# sensor_de_corriente.net
KiCad netlist of a schematic drawn in Altium Designer
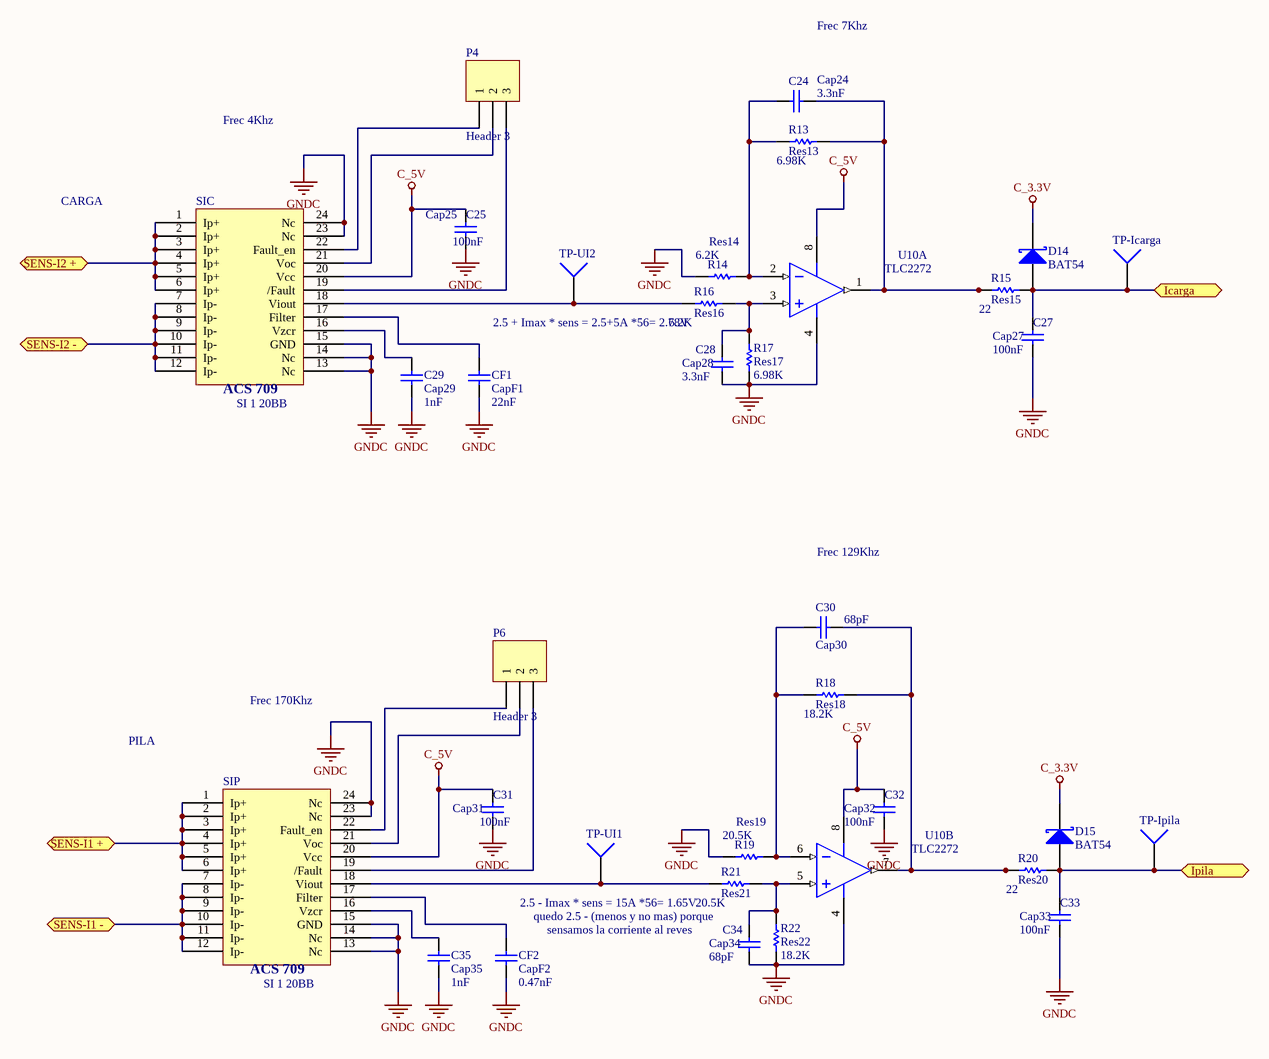
[diagram p0: sensor de corriente.SchDoc]

(export (version "E")
  (design (tool "Eeschema 10.0.6"))
  (components
    (comp (ref "C24")
      (value "Cap24")
      (footprint "RAD-0.1")
      (description "THRU MULTICAPA 50V")
      (fields (field (name "ALTIUM_VALUE") "3.3nF") (field (name "PUBLISHER") "Altium Limited"))
      (libsource (lib "Miscellaneous Devices") (part "Cap"))
    )
    (comp (ref "C25")
      (value "Cap25")
      (footprint "8-1206")
      (description "SMD MULTICAPA 50V")
      (fields (field (name "ALTIUM_VALUE") "100nF") (field (name "PUBLISHER") "Altium Limited"))
      (libsource (lib "Miscellaneous Devices") (part "Cap"))
    )
    (comp (ref "C27")
      (value "Cap27")
      (footprint "8-1206")
      (description "SMD MULTICAPA 50V")
      (fields (field (name "ALTIUM_VALUE") "100nF") (field (name "PUBLISHER") "Altium Limited"))
      (libsource (lib "Miscellaneous Devices") (part "Cap"))
    )
    (comp (ref "C28")
      (value "Cap28")
      (footprint "RAD-0.1")
      (description "THRU MULTICAPA 50V")
      (fields (field (name "ALTIUM_VALUE") "3.3nF") (field (name "PUBLISHER") "Altium Limited"))
      (libsource (lib "Miscellaneous Devices") (part "Cap"))
    )
    (comp (ref "C29")
      (value "Cap29")
      (footprint "8-1206")
      (description "SMD MULTICAPA 50V")
      (fields (field (name "ALTIUM_VALUE") "1nF") (field (name "PUBLISHER") "Altium Limited"))
      (libsource (lib "Miscellaneous Devices") (part "Cap"))
    )
    (comp (ref "C30")
      (value "Cap30")
      (footprint "RAD-0.1")
      (description "THRU MULTICAPA 50V")
      (fields (field (name "ALTIUM_VALUE") "68pF") (field (name "PUBLISHER") "Altium Limited"))
      (libsource (lib "Miscellaneous Devices") (part "Cap"))
    )
    (comp (ref "C31")
      (value "Cap31")
      (footprint "8-1206")
      (description "SMD MULTICAPA 50V")
      (fields (field (name "ALTIUM_VALUE") "100nF") (field (name "PUBLISHER") "Altium Limited"))
      (libsource (lib "Miscellaneous Devices") (part "Cap"))
    )
    (comp (ref "C32")
      (value "Cap32")
      (footprint "8-1206")
      (description "SMD MULTICAPA 50V")
      (fields (field (name "ALTIUM_VALUE") "100nF") (field (name "PUBLISHER") "Altium Limited"))
      (libsource (lib "Miscellaneous Devices") (part "Cap"))
    )
    (comp (ref "C33")
      (value "Cap33")
      (footprint "8-1206")
      (description "SMD MULTICAPA 50V")
      (fields (field (name "ALTIUM_VALUE") "100nF") (field (name "PUBLISHER") "Altium Limited"))
      (libsource (lib "Miscellaneous Devices") (part "Cap"))
    )
    (comp (ref "C34")
      (value "Cap34")
      (footprint "RAD-0.1")
      (description "THRU MULTICAPA 50V")
      (fields (field (name "ALTIUM_VALUE") "68pF") (field (name "PUBLISHER") "Altium Limited"))
      (libsource (lib "Miscellaneous Devices") (part "Cap"))
    )
    (comp (ref "C35")
      (value "Cap35")
      (footprint "8-1206")
      (description "SMD MULTICAPA 50V")
      (fields (field (name "ALTIUM_VALUE") "1nF") (field (name "PUBLISHER") "Altium Limited"))
      (libsource (lib "Miscellaneous Devices") (part "Cap"))
    )
    (comp (ref "CF1")
      (value "CapF1")
      (footprint "RAD-0.1")
      (description "SMD MULTICAPA 50V")
      (fields (field (name "ALTIUM_VALUE") "22nF") (field (name "PUBLISHER") "Altium Limited"))
      (libsource (lib "Miscellaneous Devices") (part "Cap"))
    )
    (comp (ref "CF2")
      (value "CapF2")
      (footprint "8-1206")
      (description "SMD MULTICAPA 50V")
      (fields (field (name "ALTIUM_VALUE") "0.47nF") (field (name "PUBLISHER") "Altium Limited"))
      (libsource (lib "Miscellaneous Devices") (part "Cap"))
    )
    (comp (ref "D14")
      (value "BAT54")
      (footprint "SOD123*")
      (description "SMD")
      (fields (field (name "PUBLISHER") "Altium Limited"))
      (libsource (lib "Philips Discrete Diode - Schottky") (part "BAT54"))
    )
    (comp (ref "D15")
      (value "BAT54")
      (footprint "SOD123*")
      (description "Schottky Barrier Diode SMD")
      (fields (field (name "PUBLISHER") "Altium Limited"))
      (libsource (lib "Philips Discrete Diode - Schottky") (part "BAT54"))
    )
    (comp (ref "P4")
      (value "Header 3")
      (footprint "HDR1X3*")
      (description "Header, 3-Pin")
      (fields (field (name "PUBLISHER") "Altium Limited"))
      (libsource (lib "Miscellaneous Connectors") (part "Header 3"))
    )
    (comp (ref "P6")
      (value "Header 3")
      (footprint "HDR1X3*")
      (description "Header, 3-Pin")
      (fields (field (name "PUBLISHER") "Altium Limited"))
      (libsource (lib "Miscellaneous Connectors") (part "Header 3"))
    )
    (comp (ref "R13")
      (value "Res13")
      (footprint "AXIAL-0.4")
      (description "Resistor")
      (fields (field (name "ALTIUM_VALUE") "6.98K") (field (name "PUBLISHER") "Altium Limited"))
      (libsource (lib "Miscellaneous Devices") (part "Res1"))
    )
    (comp (ref "R14")
      (value "Res14")
      (footprint "AXIAL-0.4")
      (description "Resistor")
      (fields (field (name "ALTIUM_VALUE") "6.2K") (field (name "PUBLISHER") "Altium Limited"))
      (libsource (lib "Miscellaneous Devices") (part "Res1"))
    )
    (comp (ref "R15")
      (value "Res15")
      (footprint "8-1206")
      (description "SMD 1206")
      (fields (field (name "ALTIUM_VALUE") "22") (field (name "PUBLISHER") "Altium Limited"))
      (libsource (lib "Miscellaneous Devices") (part "Res1"))
    )
    (comp (ref "R16")
      (value "Res16")
      (footprint "AXIAL-0.4")
      (description "Resistor")
      (fields (field (name "ALTIUM_VALUE") "6.2K") (field (name "PUBLISHER") "Altium Limited"))
      (libsource (lib "Miscellaneous Devices") (part "Res1"))
    )
    (comp (ref "R17")
      (value "Res17")
      (footprint "AXIAL-0.4")
      (description "Resistor")
      (fields (field (name "ALTIUM_VALUE") "6.98K") (field (name "PUBLISHER") "Altium Limited"))
      (libsource (lib "Miscellaneous Devices") (part "Res1"))
    )
    (comp (ref "R18")
      (value "Res18")
      (footprint "AXIAL-0.4")
      (description "Resistor")
      (fields (field (name "ALTIUM_VALUE") "18.2K") (field (name "PUBLISHER") "Altium Limited"))
      (libsource (lib "Miscellaneous Devices") (part "Res1"))
    )
    (comp (ref "R19")
      (value "Res19")
      (footprint "AXIAL-0.4")
      (description "Resistor")
      (fields (field (name "ALTIUM_VALUE") "20.5K") (field (name "PUBLISHER") "Altium Limited"))
      (libsource (lib "Miscellaneous Devices") (part "Res1"))
    )
    (comp (ref "R20")
      (value "Res20")
      (footprint "8-1206")
      (description "SMD 1206")
      (fields (field (name "ALTIUM_VALUE") "22") (field (name "PUBLISHER") "Altium Limited"))
      (libsource (lib "Miscellaneous Devices") (part "Res1"))
    )
    (comp (ref "R21")
      (value "Res21")
      (footprint "AXIAL-0.4")
      (description "Resistor")
      (fields (field (name "ALTIUM_VALUE") "20.5K") (field (name "PUBLISHER") "Altium Limited"))
      (libsource (lib "Miscellaneous Devices") (part "Res1"))
    )
    (comp (ref "R22")
      (value "Res22")
      (footprint "AXIAL-0.4")
      (description "Resistor")
      (fields (field (name "ALTIUM_VALUE") "18.2K") (field (name "PUBLISHER") "Altium Limited"))
      (libsource (lib "Miscellaneous Devices") (part "Res1"))
    )
    (comp (ref "SIC")
      (value "SI 1 20BB")
      (footprint "Sensor Corriente ACS 709")
      (libsource (lib "sensor corriente ACS 709") (part "Component_1"))
    )
    (comp (ref "SIP")
      (value "SI 1 20BB")
      (footprint "Sensor Corriente ACS 709")
      (libsource (lib "sensor corriente ACS 709") (part "Component_1"))
    )
    (comp (ref "TP-Icarga")
      (value "~")
      (footprint "PIN1")
      (description "Socket")
      (fields (field (name "PUBLISHER") "Altium Limited"))
      (libsource (lib "Miscellaneous Connectors") (part "Socket"))
    )
    (comp (ref "TP-Ipila")
      (value "~")
      (footprint "PIN1")
      (description "Socket")
      (fields (field (name "PUBLISHER") "Altium Limited"))
      (libsource (lib "Miscellaneous Connectors") (part "Socket"))
    )
    (comp (ref "TP-UI1")
      (value "~")
      (footprint "PIN1")
      (description "Socket")
      (fields (field (name "PUBLISHER") "Altium Limited"))
      (libsource (lib "Miscellaneous Connectors") (part "Socket"))
    )
    (comp (ref "TP-UI2")
      (value "~")
      (footprint "PIN1")
      (description "Socket")
      (fields (field (name "PUBLISHER") "Altium Limited"))
      (libsource (lib "Miscellaneous Connectors") (part "Socket"))
    )
    (comp (ref "U10")
      (value "TLC2272")
      (footprint "751-02_N")
      (description "LinCMOS Precision Dual Operational Amplifier")
      (fields (field (name "PUBLISHER") "Altium Limited"))
      (libsource (lib "TI Operational Amplifier") (part "TLC27L2ACDR"))
    )
  )
  (nets
    (net (code "1") (name "/Icarga") (class "Default")
      (node (ref "C27") (pin "1") (pinfunction "1_1") (pintype "passive"))
      (node (ref "D14") (pin "1") (pinfunction "A_1") (pintype "passive"))
      (node (ref "R15") (pin "2") (pinfunction "2_2") (pintype "passive"))
      (node (ref "TP-Icarga") (pin "1") (pinfunction "1_1") (pintype "passive"))
    )
    (net (code "2") (name "/Ipila") (class "Default")
      (node (ref "C33") (pin "1") (pinfunction "1_1") (pintype "passive"))
      (node (ref "D15") (pin "1") (pinfunction "A_1") (pintype "passive"))
      (node (ref "R20") (pin "2") (pinfunction "2_2") (pintype "passive"))
      (node (ref "TP-Ipila") (pin "1") (pinfunction "1_1") (pintype "passive"))
    )
    (net (code "3") (name "/SENS-I1 +") (class "Default")
      (node (ref "SIP") (pin "1") (pinfunction "Ip+_1") (pintype "passive"))
      (node (ref "SIP") (pin "2") (pinfunction "Ip+_2") (pintype "passive"))
      (node (ref "SIP") (pin "3") (pinfunction "Ip+_3") (pintype "passive"))
      (node (ref "SIP") (pin "4") (pinfunction "Ip+_4") (pintype "passive"))
      (node (ref "SIP") (pin "5") (pinfunction "Ip+_5") (pintype "passive"))
      (node (ref "SIP") (pin "6") (pinfunction "Ip+_6") (pintype "passive"))
    )
    (net (code "4") (name "/SENS-I1 -") (class "Default")
      (node (ref "SIP") (pin "10") (pinfunction "Ip-_10") (pintype "passive"))
      (node (ref "SIP") (pin "11") (pinfunction "Ip-_11") (pintype "passive"))
      (node (ref "SIP") (pin "12") (pinfunction "Ip-_12") (pintype "passive"))
      (node (ref "SIP") (pin "7") (pinfunction "Ip-_7") (pintype "passive"))
      (node (ref "SIP") (pin "8") (pinfunction "Ip-_8") (pintype "passive"))
      (node (ref "SIP") (pin "9") (pinfunction "Ip-_9") (pintype "passive"))
    )
    (net (code "5") (name "/SENS-I2 +") (class "Default")
      (node (ref "SIC") (pin "1") (pinfunction "Ip+_1") (pintype "passive"))
      (node (ref "SIC") (pin "2") (pinfunction "Ip+_2") (pintype "passive"))
      (node (ref "SIC") (pin "3") (pinfunction "Ip+_3") (pintype "passive"))
      (node (ref "SIC") (pin "4") (pinfunction "Ip+_4") (pintype "passive"))
      (node (ref "SIC") (pin "5") (pinfunction "Ip+_5") (pintype "passive"))
      (node (ref "SIC") (pin "6") (pinfunction "Ip+_6") (pintype "passive"))
    )
    (net (code "6") (name "/SENS-I2 -") (class "Default")
      (node (ref "SIC") (pin "10") (pinfunction "Ip-_10") (pintype "passive"))
      (node (ref "SIC") (pin "11") (pinfunction "Ip-_11") (pintype "passive"))
      (node (ref "SIC") (pin "12") (pinfunction "Ip-_12") (pintype "passive"))
      (node (ref "SIC") (pin "7") (pinfunction "Ip-_7") (pintype "passive"))
      (node (ref "SIC") (pin "8") (pinfunction "Ip-_8") (pintype "passive"))
      (node (ref "SIC") (pin "9") (pinfunction "Ip-_9") (pintype "passive"))
    )
    (net (code "7") (name "C_3.3V") (class "Default")
      (node (ref "D14") (pin "2") (pinfunction "K_2") (pintype "passive"))
      (node (ref "D15") (pin "2") (pinfunction "K_2") (pintype "passive"))
    )
    (net (code "8") (name "C_5V") (class "Default")
      (node (ref "C25") (pin "1") (pinfunction "1_1") (pintype "passive"))
      (node (ref "C31") (pin "1") (pinfunction "1_1") (pintype "passive"))
      (node (ref "C32") (pin "1") (pinfunction "1_1") (pintype "passive"))
      (node (ref "SIC") (pin "20") (pinfunction "Vcc_20") (pintype "passive"))
      (node (ref "SIP") (pin "20") (pinfunction "Vcc_20") (pintype "passive"))
      (node (ref "U10") (pin "8") (pinfunction "VDD_8") (pintype "power_in"))
    )
    (net (code "9") (name "GNDC") (class "Default")
      (node (ref "C25") (pin "2") (pinfunction "2_2") (pintype "passive"))
      (node (ref "C27") (pin "2") (pinfunction "2_2") (pintype "passive"))
      (node (ref "C28") (pin "2") (pinfunction "2_2") (pintype "passive"))
      (node (ref "C29") (pin "2") (pinfunction "2_2") (pintype "passive"))
      (node (ref "C31") (pin "2") (pinfunction "2_2") (pintype "passive"))
      (node (ref "C32") (pin "2") (pinfunction "2_2") (pintype "passive"))
      (node (ref "C33") (pin "2") (pinfunction "2_2") (pintype "passive"))
      (node (ref "C34") (pin "2") (pinfunction "2_2") (pintype "passive"))
      (node (ref "C35") (pin "2") (pinfunction "2_2") (pintype "passive"))
      (node (ref "CF1") (pin "1") (pinfunction "1_1") (pintype "passive"))
      (node (ref "CF2") (pin "1") (pinfunction "1_1") (pintype "passive"))
      (node (ref "R14") (pin "1") (pinfunction "1_1") (pintype "passive"))
      (node (ref "R17") (pin "2") (pinfunction "2_2") (pintype "passive"))
      (node (ref "R19") (pin "1") (pinfunction "1_1") (pintype "passive"))
      (node (ref "R22") (pin "2") (pinfunction "2_2") (pintype "passive"))
      (node (ref "SIC") (pin "13") (pinfunction "Nc_13") (pintype "passive"))
      (node (ref "SIC") (pin "14") (pinfunction "Nc_14") (pintype "passive"))
      (node (ref "SIC") (pin "15") (pinfunction "GND_15") (pintype "passive"))
      (node (ref "SIC") (pin "23") (pinfunction "Nc_23") (pintype "passive"))
      (node (ref "SIC") (pin "24") (pinfunction "Nc_24") (pintype "passive"))
      (node (ref "SIP") (pin "13") (pinfunction "Nc_13") (pintype "passive"))
      (node (ref "SIP") (pin "14") (pinfunction "Nc_14") (pintype "passive"))
      (node (ref "SIP") (pin "15") (pinfunction "GND_15") (pintype "passive"))
      (node (ref "SIP") (pin "23") (pinfunction "Nc_23") (pintype "passive"))
      (node (ref "SIP") (pin "24") (pinfunction "Nc_24") (pintype "passive"))
      (node (ref "U10") (pin "4") (pinfunction "GND_4") (pintype "power_in"))
    )
    (net (code "10") (name "Net-(SIC-Fault_en)") (class "Default")
      (node (ref "P4") (pin "1") (pinfunction "1_1") (pintype "passive"))
      (node (ref "SIC") (pin "22") (pinfunction "Fault_en_22") (pintype "passive"))
    )
    (net (code "11") (name "Net-(SIC-Filter)") (class "Default")
      (node (ref "CF1") (pin "2") (pinfunction "2_2") (pintype "passive"))
      (node (ref "SIC") (pin "17") (pinfunction "Filter_17") (pintype "passive"))
    )
    (net (code "12") (name "Net-(SIC-Viout)") (class "Default")
      (node (ref "R16") (pin "1") (pinfunction "1_1") (pintype "passive"))
      (node (ref "SIC") (pin "18") (pinfunction "Viout_18") (pintype "passive"))
      (node (ref "TP-UI2") (pin "1") (pinfunction "1_1") (pintype "passive"))
    )
    (net (code "13") (name "Net-(SIC-Voc)") (class "Default")
      (node (ref "P4") (pin "2") (pinfunction "2_2") (pintype "passive"))
      (node (ref "SIC") (pin "21") (pinfunction "Voc_21") (pintype "passive"))
    )
    (net (code "14") (name "Net-(SIC-Vzcr)") (class "Default")
      (node (ref "C29") (pin "1") (pinfunction "1_1") (pintype "passive"))
      (node (ref "SIC") (pin "16") (pinfunction "Vzcr_16") (pintype "passive"))
    )
    (net (code "15") (name "Net-(SIC-{slash}Fault)") (class "Default")
      (node (ref "P4") (pin "3") (pinfunction "3_3") (pintype "passive"))
      (node (ref "SIC") (pin "19") (pinfunction "/Fault_19") (pintype "passive"))
    )
    (net (code "16") (name "Net-(SIP-Fault_en)") (class "Default")
      (node (ref "P6") (pin "1") (pinfunction "1_1") (pintype "passive"))
      (node (ref "SIP") (pin "22") (pinfunction "Fault_en_22") (pintype "passive"))
    )
    (net (code "17") (name "Net-(SIP-Filter)") (class "Default")
      (node (ref "CF2") (pin "2") (pinfunction "2_2") (pintype "passive"))
      (node (ref "SIP") (pin "17") (pinfunction "Filter_17") (pintype "passive"))
    )
    (net (code "18") (name "Net-(SIP-Viout)") (class "Default")
      (node (ref "R21") (pin "1") (pinfunction "1_1") (pintype "passive"))
      (node (ref "SIP") (pin "18") (pinfunction "Viout_18") (pintype "passive"))
      (node (ref "TP-UI1") (pin "1") (pinfunction "1_1") (pintype "passive"))
    )
    (net (code "19") (name "Net-(SIP-Voc)") (class "Default")
      (node (ref "P6") (pin "2") (pinfunction "2_2") (pintype "passive"))
      (node (ref "SIP") (pin "21") (pinfunction "Voc_21") (pintype "passive"))
    )
    (net (code "20") (name "Net-(SIP-Vzcr)") (class "Default")
      (node (ref "C35") (pin "1") (pinfunction "1_1") (pintype "passive"))
      (node (ref "SIP") (pin "16") (pinfunction "Vzcr_16") (pintype "passive"))
    )
    (net (code "21") (name "Net-(SIP-{slash}Fault)") (class "Default")
      (node (ref "P6") (pin "3") (pinfunction "3_3") (pintype "passive"))
      (node (ref "SIP") (pin "19") (pinfunction "/Fault_19") (pintype "passive"))
    )
    (net (code "22") (name "Net-(U10A-IN+)") (class "Default")
      (node (ref "C28") (pin "1") (pinfunction "1_1") (pintype "passive"))
      (node (ref "R16") (pin "2") (pinfunction "2_2") (pintype "passive"))
      (node (ref "R17") (pin "1") (pinfunction "1_1") (pintype "passive"))
      (node (ref "U10") (pin "3") (pinfunction "IN+_3") (pintype "input"))
    )
    (net (code "23") (name "Net-(U10A-IN-)") (class "Default")
      (node (ref "C24") (pin "1") (pinfunction "1_1") (pintype "passive"))
      (node (ref "R13") (pin "1") (pinfunction "1_1") (pintype "passive"))
      (node (ref "R14") (pin "2") (pinfunction "2_2") (pintype "passive"))
      (node (ref "U10") (pin "2") (pinfunction "IN-_2") (pintype "input"))
    )
    (net (code "24") (name "Net-(U10A-OUT)") (class "Default")
      (node (ref "C24") (pin "2") (pinfunction "2_2") (pintype "passive"))
      (node (ref "R13") (pin "2") (pinfunction "2_2") (pintype "passive"))
      (node (ref "R15") (pin "1") (pinfunction "1_1") (pintype "passive"))
      (node (ref "U10") (pin "1") (pinfunction "OUT_1") (pintype "output"))
    )
    (net (code "25") (name "Net-(U10B-IN+)") (class "Default")
      (node (ref "C34") (pin "1") (pinfunction "1_1") (pintype "passive"))
      (node (ref "R21") (pin "2") (pinfunction "2_2") (pintype "passive"))
      (node (ref "R22") (pin "1") (pinfunction "1_1") (pintype "passive"))
      (node (ref "U10") (pin "5") (pinfunction "IN+_5") (pintype "input"))
    )
    (net (code "26") (name "Net-(U10B-IN-)") (class "Default")
      (node (ref "C30") (pin "1") (pinfunction "1_1") (pintype "passive"))
      (node (ref "R18") (pin "1") (pinfunction "1_1") (pintype "passive"))
      (node (ref "R19") (pin "2") (pinfunction "2_2") (pintype "passive"))
      (node (ref "U10") (pin "6") (pinfunction "IN-_6") (pintype "input"))
    )
    (net (code "27") (name "Net-(U10B-OUT)") (class "Default")
      (node (ref "C30") (pin "2") (pinfunction "2_2") (pintype "passive"))
      (node (ref "R18") (pin "2") (pinfunction "2_2") (pintype "passive"))
      (node (ref "R20") (pin "1") (pinfunction "1_1") (pintype "passive"))
      (node (ref "U10") (pin "7") (pinfunction "OUT_7") (pintype "output"))
    )
  )
)
